# sch_sondax3.net
KiCad netlist of a schematic drawn in EAGLE
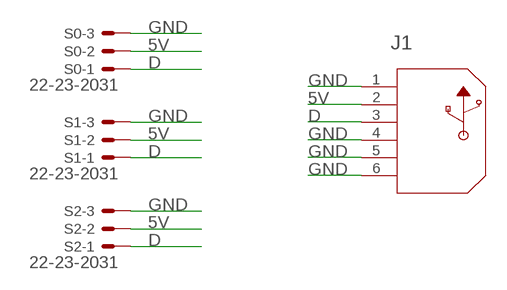
[diagram p0: schematic, sheet 1]

(export (version "E")
  (design (tool "Eeschema 10.0.6"))
  (components
    (comp (ref "J1")
      (value "292303-3")
      (footprint "eagle-import:CONN4_292303_TEC")
      (fields (field (name "COPYRIGHT") "Copyright (C) 2016 Accelerated Designs. All rights reserved"))
      (libsource (lib "eagle-import") (part "292303-3"))
    )
    (comp (ref "S0")
      (value "22-23-2031")
      (footprint "eagle-import:22-23-2031")
      (fields (field (name "MF") "MOLEX"))
      (libsource (lib "eagle-import") (part "22-23-2031"))
    )
    (comp (ref "S1")
      (value "22-23-2031")
      (footprint "eagle-import:22-23-2031")
      (fields (field (name "MF") "MOLEX"))
      (libsource (lib "eagle-import") (part "22-23-2031"))
    )
    (comp (ref "S2")
      (value "22-23-2031")
      (footprint "eagle-import:22-23-2031")
      (fields (field (name "MF") "MOLEX"))
      (libsource (lib "eagle-import") (part "22-23-2031"))
    )
  )
  (nets
    (net (code "1") (name "/5V") (class "Default")
      (node (ref "J1") (pin "2") (pinfunction "2_2") (pintype "passive"))
      (node (ref "S0") (pin "2") (pinfunction "S_2") (pintype "passive"))
      (node (ref "S1") (pin "2") (pinfunction "S_2") (pintype "passive"))
      (node (ref "S2") (pin "2") (pinfunction "S_2") (pintype "passive"))
    )
    (net (code "2") (name "/D") (class "Default")
      (node (ref "J1") (pin "3") (pinfunction "3_3") (pintype "passive"))
      (node (ref "S0") (pin "1") (pinfunction "S_1") (pintype "passive"))
      (node (ref "S1") (pin "1") (pinfunction "S_1") (pintype "passive"))
      (node (ref "S2") (pin "1") (pinfunction "S_1") (pintype "passive"))
    )
    (net (code "3") (name "/GND") (class "Default")
      (node (ref "J1") (pin "1") (pinfunction "1_1") (pintype "passive"))
      (node (ref "J1") (pin "4") (pinfunction "4_4") (pintype "passive"))
      (node (ref "J1") (pin "5") (pinfunction "5_5") (pintype "passive"))
      (node (ref "J1") (pin "6") (pinfunction "6_6") (pintype "passive"))
      (node (ref "S0") (pin "3") (pinfunction "S_3") (pintype "passive"))
      (node (ref "S1") (pin "3") (pinfunction "S_3") (pintype "passive"))
      (node (ref "S2") (pin "3") (pinfunction "S_3") (pintype "passive"))
    )
  )
)
